# Sheet3.net
KiCad netlist of a schematic drawn in Altium Designer
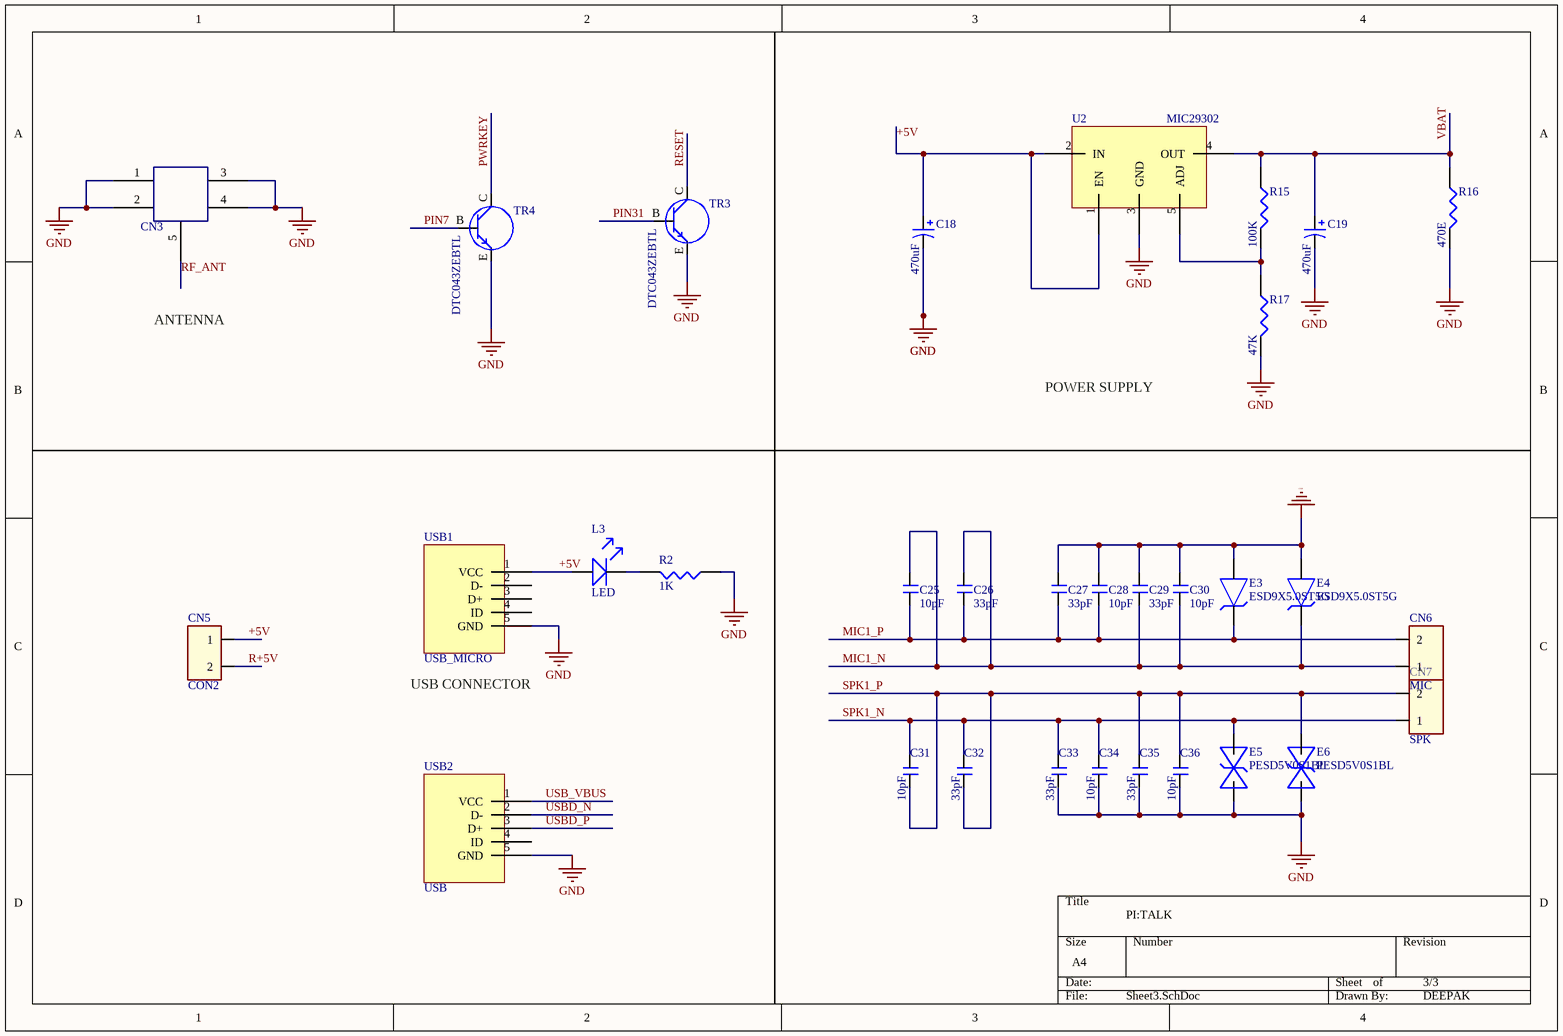
[diagram p0: Sheet3.SchDoc]

(export (version "E")
  (design (tool "Eeschema 10.0.6"))
  (components
    (comp (ref "C18")
      (value "470uF")
      (footprint "Cap_Tantalum C-CASE_AVX")
      (libsource (lib "dxp_pasl_lib") (part "CAP_ELEC"))
    )
    (comp (ref "C19")
      (value "470uF")
      (footprint "Cap_Tantalum C-CASE_AVX")
      (libsource (lib "dxp_pasl_lib") (part "CAP_ELEC"))
    )
    (comp (ref "C25")
      (value "10pF")
      (footprint "CAP_0603_NONPOLAR")
      (libsource (lib "dxp_pasl_lib") (part "CAP_NONPOLAR"))
    )
    (comp (ref "C26")
      (value "33pF")
      (footprint "CAP_0603_NONPOLAR")
      (libsource (lib "dxp_pasl_lib") (part "CAP_NONPOLAR"))
    )
    (comp (ref "C27")
      (value "33pF")
      (footprint "CAP_0603_NONPOLAR")
      (libsource (lib "dxp_pasl_lib") (part "CAP_NONPOLAR"))
    )
    (comp (ref "C28")
      (value "10pF")
      (footprint "CAP_0603_NONPOLAR")
      (libsource (lib "dxp_pasl_lib") (part "CAP_NONPOLAR"))
    )
    (comp (ref "C29")
      (value "33pF")
      (footprint "CAP_0603_NONPOLAR")
      (libsource (lib "dxp_pasl_lib") (part "CAP_NONPOLAR"))
    )
    (comp (ref "C30")
      (value "10pF")
      (footprint "CAP_0603_NONPOLAR")
      (libsource (lib "dxp_pasl_lib") (part "CAP_NONPOLAR"))
    )
    (comp (ref "C31")
      (value "10pF")
      (footprint "CAP_0603_NONPOLAR")
      (libsource (lib "dxp_pasl_lib") (part "CAP_NONPOLAR"))
    )
    (comp (ref "C32")
      (value "33pF")
      (footprint "CAP_0603_NONPOLAR")
      (libsource (lib "dxp_pasl_lib") (part "CAP_NONPOLAR"))
    )
    (comp (ref "C33")
      (value "33pF")
      (footprint "CAP_0603_NONPOLAR")
      (libsource (lib "dxp_pasl_lib") (part "CAP_NONPOLAR"))
    )
    (comp (ref "C34")
      (value "10pF")
      (footprint "CAP_0603_NONPOLAR")
      (libsource (lib "dxp_pasl_lib") (part "CAP_NONPOLAR"))
    )
    (comp (ref "C35")
      (value "33pF")
      (footprint "CAP_0603_NONPOLAR")
      (libsource (lib "dxp_pasl_lib") (part "CAP_NONPOLAR"))
    )
    (comp (ref "C36")
      (value "10pF")
      (footprint "CAP_0603_NONPOLAR")
      (libsource (lib "dxp_pasl_lib") (part "CAP_NONPOLAR"))
    )
    (comp (ref "CN3")
      (value "SMA  CONNECTOR")
      (footprint "SMA_CONNECTOR")
      (libsource (lib "dxp_pasl_lib") (part "SMA CONNECTOR"))
    )
    (comp (ref "CN5") (value "CON2") (footprint "CON2_BJ") (libsource (lib "") (part "CON2_1")))
    (comp (ref "CN6") (value "MIC") (footprint "CON2_BJ") (libsource (lib "dxp_pasl_lib") (part "CON2")))
    (comp (ref "CN7") (value "SPK") (footprint "CON2_BJ") (libsource (lib "dxp_pasl_lib") (part "CON2")))
    (comp (ref "E3")
      (value "ESD9X5.0ST5G")
      (footprint "SOD923")
      (libsource (lib "dxp_pasl_lib") (part "ESD9X5.0ST5G"))
    )
    (comp (ref "E4")
      (value "ESD9X5.0ST5G")
      (footprint "SOD923")
      (libsource (lib "dxp_pasl_lib") (part "ESD9X5.0ST5G"))
    )
    (comp (ref "E5")
      (value "PESD5V0S1BL")
      (footprint "SOD882")
      (libsource (lib "dxp_pasl_lib") (part "PESD5V0S1BL"))
    )
    (comp (ref "E6")
      (value "PESD5V0S1BL")
      (footprint "SOD882")
      (libsource (lib "dxp_pasl_lib") (part "PESD5V0S1BL"))
    )
    (comp (ref "L3") (value "LED") (footprint "LED_0603_neg") (libsource (lib "dxp_pasl_lib") (part "LED")))
    (comp (ref "R2") (value "1K") (footprint "0603") (libsource (lib "dxp_pasl_lib") (part "RES")))
    (comp (ref "R15") (value "100K") (footprint "0603") (libsource (lib "dxp_pasl_lib") (part "RES")))
    (comp (ref "R16") (value "470E") (footprint "0603") (libsource (lib "dxp_pasl_lib") (part "RES")))
    (comp (ref "R17") (value "47K") (footprint "0603") (libsource (lib "dxp_pasl_lib") (part "RES")))
    (comp (ref "TR3")
      (value "DTC043ZEBTL")
      (footprint "DTC043ZEBTL")
      (libsource (lib "dxp_pasl_lib") (part "DTC043ZEBTL"))
    )
    (comp (ref "TR4")
      (value "DTC043ZEBTL")
      (footprint "DTC043ZEBTL")
      (libsource (lib "dxp_pasl_lib") (part "DTC043ZEBTL"))
    )
    (comp (ref "U2")
      (value "MIC29302")
      (footprint "MIC29302")
      (libsource (lib "Integrated_Library") (part "MIC29302"))
    )
    (comp (ref "USB1")
      (value "USB_MICRO")
      (footprint "USB_MICRO")
      (libsource (lib "lripl_intlib") (part "USB_MICRO"))
    )
    (comp (ref "USB2")
      (value "USB")
      (footprint "USB_MICRO")
      (libsource (lib "dxp_pasl_lib") (part "USB_MICRO"))
    )
  )
  (nets
    (net (code "1") (name "/+5V") (class "Default")
      (node (ref "C18") (pin "A") (pinfunction "A_A") (pintype "passive"))
      (node (ref "CN5") (pin "1") (pinfunction "1_1") (pintype "passive"))
      (node (ref "L3") (pin "A") (pinfunction "A_A") (pintype "passive"))
      (node (ref "U2") (pin "1") (pinfunction "EN_1") (pintype "passive"))
      (node (ref "U2") (pin "2") (pinfunction "IN_2") (pintype "passive"))
      (node (ref "USB1") (pin "1") (pinfunction "VCC_1") (pintype "passive"))
    )
    (net (code "2") (name "/MIC1_N") (class "Default")
      (node (ref "C25") (pin "1") (pinfunction "1_1") (pintype "passive"))
      (node (ref "C26") (pin "1") (pinfunction "1_1") (pintype "passive"))
      (node (ref "C29") (pin "2") (pinfunction "2_2") (pintype "passive"))
      (node (ref "C30") (pin "2") (pinfunction "2_2") (pintype "passive"))
      (node (ref "CN6") (pin "1") (pinfunction "1_1") (pintype "passive"))
      (node (ref "E4") (pin "1") (pinfunction "C_1") (pintype "passive"))
    )
    (net (code "3") (name "/MIC1_P") (class "Default")
      (node (ref "C25") (pin "2") (pinfunction "2_2") (pintype "passive"))
      (node (ref "C26") (pin "2") (pinfunction "2_2") (pintype "passive"))
      (node (ref "C27") (pin "2") (pinfunction "2_2") (pintype "passive"))
      (node (ref "C28") (pin "2") (pinfunction "2_2") (pintype "passive"))
      (node (ref "CN6") (pin "2") (pinfunction "2_2") (pintype "passive"))
      (node (ref "E3") (pin "1") (pinfunction "C_1") (pintype "passive"))
    )
    (net (code "4") (name "/PIN7") (class "Default")
      (node (ref "TR4") (pin "B") (pinfunction "B_B") (pintype "passive"))
    )
    (net (code "5") (name "/PIN31") (class "Default")
      (node (ref "TR3") (pin "B") (pinfunction "B_B") (pintype "passive"))
    )
    (net (code "6") (name "/PWRKEY") (class "Default")
      (node (ref "TR4") (pin "C") (pinfunction "C_C") (pintype "passive"))
    )
    (net (code "7") (name "/R+5V") (class "Default")
      (node (ref "CN5") (pin "2") (pinfunction "2_2") (pintype "passive"))
    )
    (net (code "8") (name "/RESET") (class "Default")
      (node (ref "TR3") (pin "C") (pinfunction "C_C") (pintype "passive"))
    )
    (net (code "9") (name "/RF_ANT") (class "Default")
      (node (ref "CN3") (pin "5") (pinfunction "5_5") (pintype "passive"))
    )
    (net (code "10") (name "/SPK1_N") (class "Default")
      (node (ref "C31") (pin "2") (pinfunction "2_2") (pintype "passive"))
      (node (ref "C32") (pin "2") (pinfunction "2_2") (pintype "passive"))
      (node (ref "C33") (pin "2") (pinfunction "2_2") (pintype "passive"))
      (node (ref "C34") (pin "2") (pinfunction "2_2") (pintype "passive"))
      (node (ref "CN7") (pin "1") (pinfunction "1_1") (pintype "passive"))
      (node (ref "E5") (pin "2") (pinfunction "A_2") (pintype "passive"))
    )
    (net (code "11") (name "/SPK1_P") (class "Default")
      (node (ref "C31") (pin "1") (pinfunction "1_1") (pintype "passive"))
      (node (ref "C32") (pin "1") (pinfunction "1_1") (pintype "passive"))
      (node (ref "C35") (pin "2") (pinfunction "2_2") (pintype "passive"))
      (node (ref "C36") (pin "2") (pinfunction "2_2") (pintype "passive"))
      (node (ref "CN7") (pin "2") (pinfunction "2_2") (pintype "passive"))
      (node (ref "E6") (pin "2") (pinfunction "A_2") (pintype "passive"))
    )
    (net (code "12") (name "/USBD_N") (class "Default")
      (node (ref "USB2") (pin "2") (pinfunction "D-_2") (pintype "passive"))
    )
    (net (code "13") (name "/USBD_P") (class "Default")
      (node (ref "USB2") (pin "3") (pinfunction "D+_3") (pintype "passive"))
    )
    (net (code "14") (name "/USB_VBUS") (class "Default")
      (node (ref "USB2") (pin "1") (pinfunction "VCC_1") (pintype "passive"))
    )
    (net (code "15") (name "/VBAT") (class "Default")
      (node (ref "C19") (pin "A") (pinfunction "A_A") (pintype "passive"))
      (node (ref "R15") (pin "1") (pinfunction "1_1") (pintype "passive"))
      (node (ref "R16") (pin "1") (pinfunction "1_1") (pintype "passive"))
      (node (ref "U2") (pin "4") (pinfunction "OUT_4") (pintype "passive"))
    )
    (net (code "16") (name "GND") (class "Default")
      (node (ref "C18") (pin "K") (pinfunction "K_K") (pintype "passive"))
      (node (ref "C19") (pin "K") (pinfunction "K_K") (pintype "passive"))
      (node (ref "C27") (pin "1") (pinfunction "1_1") (pintype "passive"))
      (node (ref "C28") (pin "1") (pinfunction "1_1") (pintype "passive"))
      (node (ref "C29") (pin "1") (pinfunction "1_1") (pintype "passive"))
      (node (ref "C30") (pin "1") (pinfunction "1_1") (pintype "passive"))
      (node (ref "C33") (pin "1") (pinfunction "1_1") (pintype "passive"))
      (node (ref "C34") (pin "1") (pinfunction "1_1") (pintype "passive"))
      (node (ref "C35") (pin "1") (pinfunction "1_1") (pintype "passive"))
      (node (ref "C36") (pin "1") (pinfunction "1_1") (pintype "passive"))
      (node (ref "CN3") (pin "1") (pinfunction "1_1") (pintype "passive"))
      (node (ref "CN3") (pin "2") (pinfunction "2_2") (pintype "passive"))
      (node (ref "CN3") (pin "3") (pinfunction "3_3") (pintype "passive"))
      (node (ref "CN3") (pin "4") (pinfunction "4_4") (pintype "passive"))
      (node (ref "E3") (pin "2") (pinfunction "A_2") (pintype "passive"))
      (node (ref "E4") (pin "2") (pinfunction "A_2") (pintype "passive"))
      (node (ref "E5") (pin "1") (pinfunction "C_1") (pintype "passive"))
      (node (ref "E6") (pin "1") (pinfunction "C_1") (pintype "passive"))
      (node (ref "R16") (pin "2") (pinfunction "2_2") (pintype "passive"))
      (node (ref "R17") (pin "2") (pinfunction "2_2") (pintype "passive"))
      (node (ref "R2") (pin "1") (pinfunction "1_1") (pintype "passive"))
      (node (ref "TR3") (pin "E") (pinfunction "E_E") (pintype "passive"))
      (node (ref "TR4") (pin "E") (pinfunction "E_E") (pintype "passive"))
      (node (ref "U2") (pin "3") (pinfunction "GND_3") (pintype "passive"))
      (node (ref "USB1") (pin "5") (pinfunction "GND_5") (pintype "passive"))
      (node (ref "USB2") (pin "5") (pinfunction "GND_5") (pintype "passive"))
    )
    (net (code "17") (name "Net-(L3-PadK)") (class "Default")
      (node (ref "L3") (pin "K") (pinfunction "K_K") (pintype "passive"))
      (node (ref "R2") (pin "2") (pinfunction "2_2") (pintype "passive"))
    )
    (net (code "18") (name "Net-(U2-ADJ)") (class "Default")
      (node (ref "R15") (pin "2") (pinfunction "2_2") (pintype "passive"))
      (node (ref "R17") (pin "1") (pinfunction "1_1") (pintype "passive"))
      (node (ref "U2") (pin "5") (pinfunction "ADJ_5") (pintype "passive"))
    )
    (net (code "19") (name "unconnected-(USB1-D+-Pad3)") (class "Default")
      (node (ref "USB1") (pin "3") (pinfunction "D+_3") (pintype "passive"))
    )
    (net (code "20") (name "unconnected-(USB1-D--Pad2)") (class "Default")
      (node (ref "USB1") (pin "2") (pinfunction "D-_2") (pintype "passive"))
    )
    (net (code "21") (name "unconnected-(USB1-ID-Pad4)") (class "Default")
      (node (ref "USB1") (pin "4") (pinfunction "ID_4") (pintype "passive"))
    )
    (net (code "22") (name "unconnected-(USB2-ID-Pad4)") (class "Default")
      (node (ref "USB2") (pin "4") (pinfunction "ID_4") (pintype "passive"))
    )
  )
)
